# PT2399.net
KiCad netlist of a schematic drawn in Altium Designer
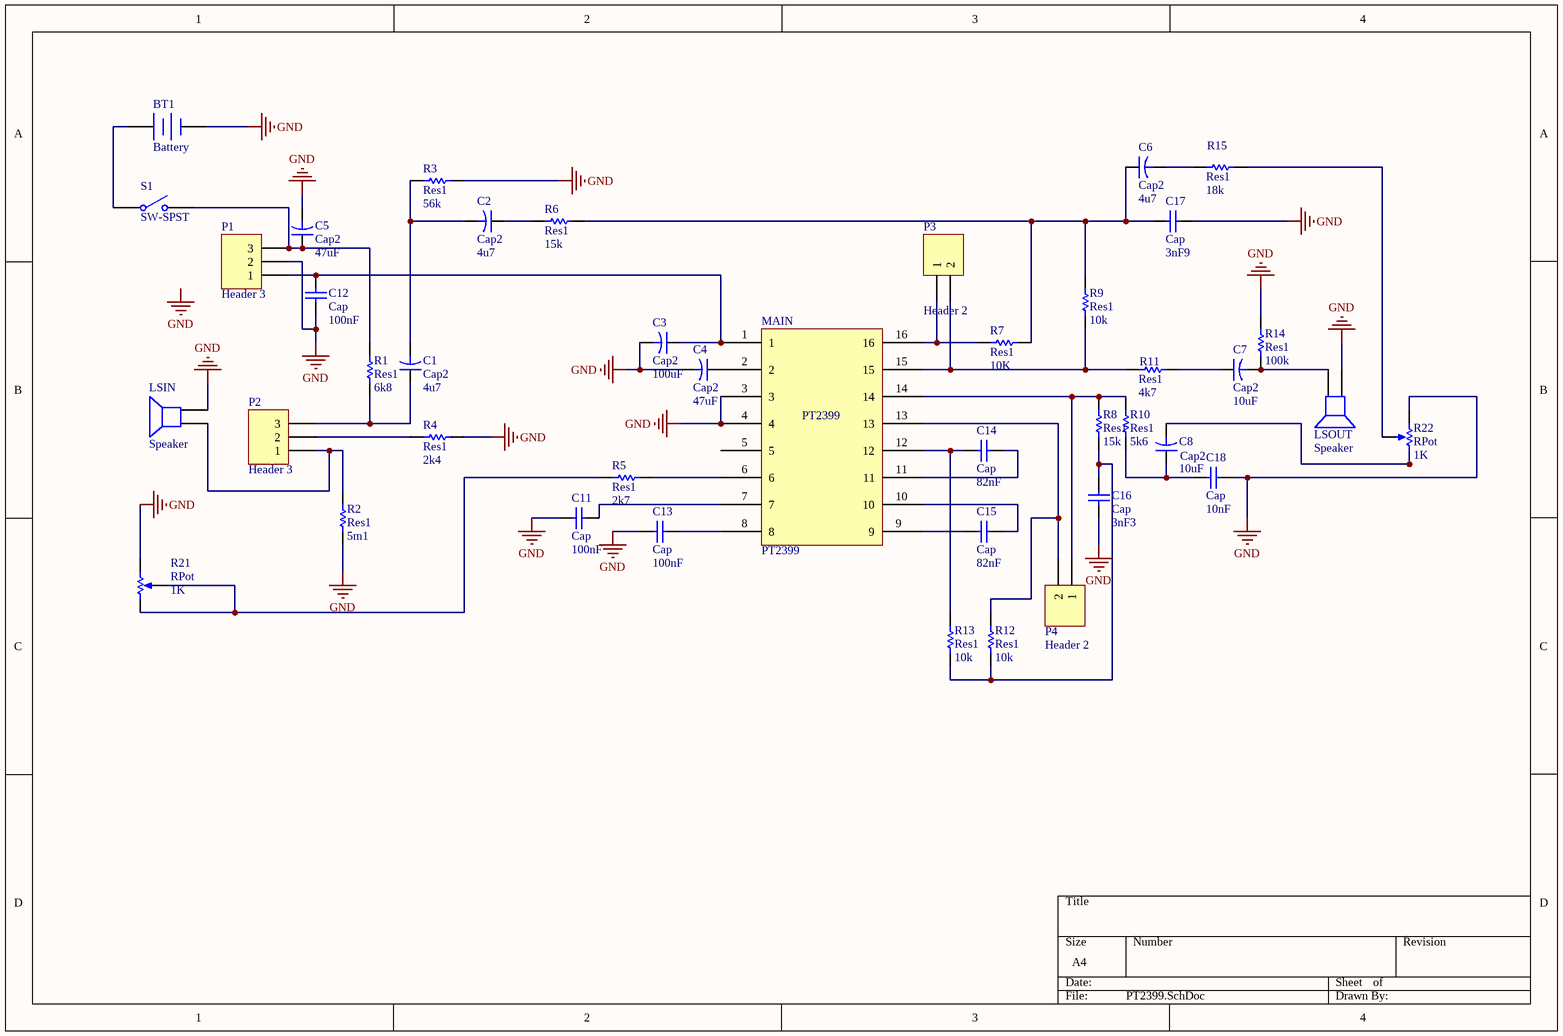
[diagram p0: PT2399.SchDoc]

(export (version "E")
  (design (tool "Eeschema 10.0.6"))
  (components
    (comp (ref "BT1")
      (value "Battery")
      (footprint "BAT-2")
      (description "Multicell Battery")
      (fields (field (name "PUBLISHER") "Altium Limited"))
      (libsource (lib "Miscellaneous Devices") (part "Battery"))
    )
    (comp (ref "C1")
      (value "Cap2")
      (footprint "CAPR5-4X5")
      (description "Capacitor")
      (fields (field (name "ALTIUM_VALUE") "4u7") (field (name "PUBLISHER") "Altium Limited"))
      (libsource (lib "Miscellaneous Devices") (part "Cap2"))
    )
    (comp (ref "C2")
      (value "Cap2")
      (footprint "CAPR5-4X5")
      (description "Capacitor")
      (fields (field (name "ALTIUM_VALUE") "4u7") (field (name "PUBLISHER") "Altium Limited"))
      (libsource (lib "Miscellaneous Devices") (part "Cap2"))
    )
    (comp (ref "C3")
      (value "Cap2")
      (footprint "CAPR5-4X5")
      (description "Capacitor")
      (fields (field (name "ALTIUM_VALUE") "100uF") (field (name "PUBLISHER") "Altium Limited"))
      (libsource (lib "Miscellaneous Devices") (part "Cap2"))
    )
    (comp (ref "C4")
      (value "Cap2")
      (footprint "CAPR5-4X5")
      (description "Capacitor")
      (fields (field (name "ALTIUM_VALUE") "47uF") (field (name "PUBLISHER") "Altium Limited"))
      (libsource (lib "Miscellaneous Devices") (part "Cap2"))
    )
    (comp (ref "C5")
      (value "Cap2")
      (footprint "CAPR5-4X5")
      (description "Capacitor")
      (fields (field (name "ALTIUM_VALUE") "47uF") (field (name "PUBLISHER") "Altium Limited"))
      (libsource (lib "Miscellaneous Devices") (part "Cap2"))
    )
    (comp (ref "C6")
      (value "Cap2")
      (footprint "CAPR5-4X5")
      (description "Capacitor")
      (fields (field (name "ALTIUM_VALUE") "4u7") (field (name "PUBLISHER") "Altium Limited"))
      (libsource (lib "Miscellaneous Devices") (part "Cap2"))
    )
    (comp (ref "C7")
      (value "Cap2")
      (footprint "CAPR5-4X5")
      (description "Capacitor")
      (fields (field (name "ALTIUM_VALUE") "10uF") (field (name "PUBLISHER") "Altium Limited"))
      (libsource (lib "Miscellaneous Devices") (part "Cap2"))
    )
    (comp (ref "C8")
      (value "Cap2")
      (footprint "CAPR5-4X5")
      (description "Capacitor")
      (fields (field (name "ALTIUM_VALUE") "10uF") (field (name "PUBLISHER") "Altium Limited"))
      (libsource (lib "Miscellaneous Devices") (part "Cap2"))
    )
    (comp (ref "C11")
      (value "Cap")
      (footprint "RAD-0.3")
      (description "Capacitor")
      (fields (field (name "ALTIUM_VALUE") "100nF") (field (name "PUBLISHER") "Altium Limited"))
      (libsource (lib "Miscellaneous Devices") (part "Cap"))
    )
    (comp (ref "C12")
      (value "Cap")
      (footprint "RAD-0.3")
      (description "Capacitor")
      (fields (field (name "ALTIUM_VALUE") "100nF") (field (name "PUBLISHER") "Altium Limited"))
      (libsource (lib "Miscellaneous Devices") (part "Cap"))
    )
    (comp (ref "C13")
      (value "Cap")
      (footprint "RAD-0.3")
      (description "Capacitor")
      (fields (field (name "ALTIUM_VALUE") "100nF") (field (name "PUBLISHER") "Altium Limited"))
      (libsource (lib "Miscellaneous Devices") (part "Cap"))
    )
    (comp (ref "C14")
      (value "Cap")
      (footprint "RAD-0.3")
      (description "Capacitor")
      (fields (field (name "ALTIUM_VALUE") "82nF") (field (name "PUBLISHER") "Altium Limited"))
      (libsource (lib "Miscellaneous Devices") (part "Cap"))
    )
    (comp (ref "C15")
      (value "Cap")
      (footprint "RAD-0.3")
      (description "Capacitor")
      (fields (field (name "ALTIUM_VALUE") "82nF") (field (name "PUBLISHER") "Altium Limited"))
      (libsource (lib "Miscellaneous Devices") (part "Cap"))
    )
    (comp (ref "C16")
      (value "Cap")
      (footprint "RAD-0.3")
      (description "Capacitor")
      (fields (field (name "ALTIUM_VALUE") "3nF3") (field (name "PUBLISHER") "Altium Limited"))
      (libsource (lib "Miscellaneous Devices") (part "Cap"))
    )
    (comp (ref "C17")
      (value "Cap")
      (footprint "RAD-0.3")
      (description "Capacitor")
      (fields (field (name "ALTIUM_VALUE") "3nF9") (field (name "PUBLISHER") "Altium Limited"))
      (libsource (lib "Miscellaneous Devices") (part "Cap"))
    )
    (comp (ref "C18")
      (value "Cap")
      (footprint "RAD-0.3")
      (description "Capacitor")
      (fields (field (name "ALTIUM_VALUE") "10nF") (field (name "PUBLISHER") "Altium Limited"))
      (libsource (lib "Miscellaneous Devices") (part "Cap"))
    )
    (comp (ref "LSIN")
      (value "Speaker")
      (footprint "PIN2")
      (description "Loudspeaker")
      (fields (field (name "PUBLISHER") "Altium Limited"))
      (libsource (lib "Miscellaneous Devices") (part "Speaker"))
    )
    (comp (ref "LSOUT")
      (value "Speaker")
      (footprint "PIN2")
      (description "Loudspeaker")
      (fields (field (name "PUBLISHER") "Altium Limited"))
      (libsource (lib "Miscellaneous Devices") (part "Speaker"))
    )
    (comp (ref "MAIN") (value "PT2399") (footprint "PT2399") (libsource (lib "Schlib1") (part "PT2399")))
    (comp (ref "P1")
      (value "Header 3")
      (footprint "HDR1X3")
      (description "Header, 3-Pin")
      (fields (field (name "PUBLISHER") "Altium Limited"))
      (libsource (lib "Miscellaneous Connectors") (part "Header 3"))
    )
    (comp (ref "P2")
      (value "Header 3")
      (footprint "HDR1X3")
      (description "Header, 3-Pin")
      (fields (field (name "PUBLISHER") "Altium Limited"))
      (libsource (lib "Miscellaneous Connectors") (part "Header 3"))
    )
    (comp (ref "P3")
      (value "Header 2")
      (footprint "HDR1X2")
      (description "Header, 2-Pin")
      (fields (field (name "PUBLISHER") "Altium Limited"))
      (libsource (lib "Miscellaneous Connectors") (part "Header 2"))
    )
    (comp (ref "P4")
      (value "Header 2")
      (footprint "HDR1X2")
      (description "Header, 2-Pin")
      (fields (field (name "PUBLISHER") "Altium Limited"))
      (libsource (lib "") (part "Header 2_1"))
    )
    (comp (ref "R1")
      (value "Res1")
      (footprint "AXIAL-0.3")
      (description "Resistor")
      (fields (field (name "ALTIUM_VALUE") "6k8") (field (name "PUBLISHER") "Altium Limited"))
      (libsource (lib "Miscellaneous Devices") (part "Res1"))
    )
    (comp (ref "R2")
      (value "Res1")
      (footprint "AXIAL-0.3")
      (description "Resistor")
      (fields (field (name "ALTIUM_VALUE") "5m1") (field (name "PUBLISHER") "Altium Limited"))
      (libsource (lib "Miscellaneous Devices") (part "Res1"))
    )
    (comp (ref "R3")
      (value "Res1")
      (footprint "AXIAL-0.3")
      (description "Resistor")
      (fields (field (name "ALTIUM_VALUE") "56k") (field (name "PUBLISHER") "Altium Limited"))
      (libsource (lib "Miscellaneous Devices") (part "Res1"))
    )
    (comp (ref "R4")
      (value "Res1")
      (footprint "AXIAL-0.3")
      (description "Resistor")
      (fields (field (name "ALTIUM_VALUE") "2k4") (field (name "PUBLISHER") "Altium Limited"))
      (libsource (lib "Miscellaneous Devices") (part "Res1"))
    )
    (comp (ref "R5")
      (value "Res1")
      (footprint "AXIAL-0.3")
      (description "Resistor")
      (fields (field (name "ALTIUM_VALUE") "2k7") (field (name "PUBLISHER") "Altium Limited"))
      (libsource (lib "Miscellaneous Devices") (part "Res1"))
    )
    (comp (ref "R6")
      (value "Res1")
      (footprint "AXIAL-0.3")
      (description "Resistor")
      (fields (field (name "ALTIUM_VALUE") "15k") (field (name "PUBLISHER") "Altium Limited"))
      (libsource (lib "Miscellaneous Devices") (part "Res1"))
    )
    (comp (ref "R7")
      (value "Res1")
      (footprint "AXIAL-0.3")
      (description "Resistor")
      (fields (field (name "ALTIUM_VALUE") "10K") (field (name "PUBLISHER") "Altium Limited"))
      (libsource (lib "Miscellaneous Devices") (part "Res1"))
    )
    (comp (ref "R8")
      (value "Res1")
      (footprint "AXIAL-0.3")
      (description "Resistor")
      (fields (field (name "ALTIUM_VALUE") "15k") (field (name "PUBLISHER") "Altium Limited"))
      (libsource (lib "Miscellaneous Devices") (part "Res1"))
    )
    (comp (ref "R9")
      (value "Res1")
      (footprint "AXIAL-0.3")
      (description "Resistor")
      (fields (field (name "ALTIUM_VALUE") "10k") (field (name "PUBLISHER") "Altium Limited"))
      (libsource (lib "Miscellaneous Devices") (part "Res1"))
    )
    (comp (ref "R10")
      (value "Res1")
      (footprint "AXIAL-0.3")
      (description "Resistor")
      (fields (field (name "ALTIUM_VALUE") "5k6") (field (name "PUBLISHER") "Altium Limited"))
      (libsource (lib "Miscellaneous Devices") (part "Res1"))
    )
    (comp (ref "R11")
      (value "Res1")
      (footprint "AXIAL-0.3")
      (description "Resistor")
      (fields (field (name "ALTIUM_VALUE") "4k7") (field (name "PUBLISHER") "Altium Limited"))
      (libsource (lib "Miscellaneous Devices") (part "Res1"))
    )
    (comp (ref "R12")
      (value "Res1")
      (footprint "AXIAL-0.3")
      (description "Resistor")
      (fields (field (name "ALTIUM_VALUE") "10k") (field (name "PUBLISHER") "Altium Limited"))
      (libsource (lib "Miscellaneous Devices") (part "Res1"))
    )
    (comp (ref "R13")
      (value "Res1")
      (footprint "AXIAL-0.3")
      (description "Resistor")
      (fields (field (name "ALTIUM_VALUE") "10k") (field (name "PUBLISHER") "Altium Limited"))
      (libsource (lib "Miscellaneous Devices") (part "Res1"))
    )
    (comp (ref "R14")
      (value "Res1")
      (footprint "AXIAL-0.3")
      (description "Resistor")
      (fields (field (name "ALTIUM_VALUE") "100k") (field (name "PUBLISHER") "Altium Limited"))
      (libsource (lib "Miscellaneous Devices") (part "Res1"))
    )
    (comp (ref "R15")
      (value "Res1")
      (footprint "AXIAL-0.3")
      (description "Resistor")
      (fields (field (name "ALTIUM_VALUE") "18k") (field (name "PUBLISHER") "Altium Limited"))
      (libsource (lib "Miscellaneous Devices") (part "Res1"))
    )
    (comp (ref "R21")
      (value "RPot")
      (footprint "7805")
      (description "Potentiometer")
      (fields (field (name "ALTIUM_VALUE") "1K") (field (name "PUBLISHER") "Altium Limited"))
      (libsource (lib "Miscellaneous Devices") (part "RPot"))
    )
    (comp (ref "R22")
      (value "RPot")
      (footprint "7805")
      (description "Potentiometer")
      (fields (field (name "ALTIUM_VALUE") "1K") (field (name "PUBLISHER") "Altium Limited"))
      (libsource (lib "Miscellaneous Devices") (part "RPot"))
    )
    (comp (ref "S1")
      (value "SW-SPST")
      (footprint "SPST-2")
      (description "Single-Pole, Single-Throw Switch")
      (fields (field (name "PUBLISHER") "Altium Limited"))
      (libsource (lib "Miscellaneous Devices") (part "SW-SPST"))
    )
  )
  (nets
    (net (code "1") (name "GND") (class "Default")
      (node (ref "BT1") (pin "2") (pinfunction "-_2") (pintype "passive"))
      (node (ref "C11") (pin "1") (pinfunction "1_1") (pintype "passive"))
      (node (ref "C12") (pin "1") (pinfunction "1_1") (pintype "passive"))
      (node (ref "C13") (pin "1") (pinfunction "1_1") (pintype "passive"))
      (node (ref "C16") (pin "1") (pinfunction "1_1") (pintype "passive"))
      (node (ref "C17") (pin "1") (pinfunction "1_1") (pintype "passive"))
      (node (ref "C18") (pin "2") (pinfunction "2_2") (pintype "passive"))
      (node (ref "C3") (pin "2") (pinfunction "2_2") (pintype "passive"))
      (node (ref "C4") (pin "2") (pinfunction "2_2") (pintype "passive"))
      (node (ref "C5") (pin "2") (pinfunction "2_2") (pintype "passive"))
      (node (ref "LSIN") (pin "2") (pinfunction "2_2") (pintype "passive"))
      (node (ref "LSOUT") (pin "1") (pinfunction "1_1") (pintype "passive"))
      (node (ref "MAIN") (pin "3") (pinfunction "3_3") (pintype "passive"))
      (node (ref "MAIN") (pin "4") (pinfunction "4_4") (pintype "passive"))
      (node (ref "P1") (pin "2") (pinfunction "2_2") (pintype "passive"))
      (node (ref "R14") (pin "2") (pinfunction "2_2") (pintype "passive"))
      (node (ref "R2") (pin "1") (pinfunction "1_1") (pintype "passive"))
      (node (ref "R21") (pin "2") (pinfunction "BOT_2") (pintype "passive"))
      (node (ref "R22") (pin "1") (pinfunction "TOP_1") (pintype "passive"))
      (node (ref "R3") (pin "1") (pinfunction "1_1") (pintype "passive"))
      (node (ref "R4") (pin "2") (pinfunction "2_2") (pintype "passive"))
    )
    (net (code "2") (name "Net-(BT1-+)") (class "Default")
      (node (ref "BT1") (pin "1") (pinfunction "+_1") (pintype "passive"))
      (node (ref "S1") (pin "1") (pinfunction "COMMON_1") (pintype "passive"))
    )
    (net (code "3") (name "Net-(C1-Pad1)") (class "Default")
      (node (ref "C1") (pin "1") (pinfunction "1_1") (pintype "passive"))
      (node (ref "P2") (pin "3") (pinfunction "3_3") (pintype "passive"))
      (node (ref "R1") (pin "1") (pinfunction "1_1") (pintype "passive"))
    )
    (net (code "4") (name "Net-(C1-Pad2)") (class "Default")
      (node (ref "C1") (pin "2") (pinfunction "2_2") (pintype "passive"))
      (node (ref "C2") (pin "2") (pinfunction "2_2") (pintype "passive"))
      (node (ref "R3") (pin "2") (pinfunction "2_2") (pintype "passive"))
    )
    (net (code "5") (name "Net-(C2-Pad1)") (class "Default")
      (node (ref "C2") (pin "1") (pinfunction "1_1") (pintype "passive"))
      (node (ref "R6") (pin "1") (pinfunction "1_1") (pintype "passive"))
    )
    (net (code "6") (name "Net-(C4-Pad1)") (class "Default")
      (node (ref "C4") (pin "1") (pinfunction "1_1") (pintype "passive"))
      (node (ref "MAIN") (pin "2") (pinfunction "2_2") (pintype "passive"))
    )
    (net (code "7") (name "Net-(C6-Pad2)") (class "Default")
      (node (ref "C6") (pin "2") (pinfunction "2_2") (pintype "passive"))
      (node (ref "R15") (pin "1") (pinfunction "1_1") (pintype "passive"))
    )
    (net (code "8") (name "Net-(C7-Pad1)") (class "Default")
      (node (ref "C7") (pin "1") (pinfunction "1_1") (pintype "passive"))
      (node (ref "R11") (pin "2") (pinfunction "2_2") (pintype "passive"))
    )
    (net (code "9") (name "Net-(C7-Pad2)") (class "Default")
      (node (ref "C7") (pin "2") (pinfunction "2_2") (pintype "passive"))
      (node (ref "LSOUT") (pin "2") (pinfunction "2_2") (pintype "passive"))
      (node (ref "R14") (pin "1") (pinfunction "1_1") (pintype "passive"))
    )
    (net (code "10") (name "Net-(C11-Pad2)") (class "Default")
      (node (ref "C11") (pin "2") (pinfunction "2_2") (pintype "passive"))
      (node (ref "MAIN") (pin "7") (pinfunction "7_7") (pintype "passive"))
    )
    (net (code "11") (name "Net-(C12-Pad2)") (class "Default")
      (node (ref "C12") (pin "2") (pinfunction "2_2") (pintype "passive"))
      (node (ref "C3") (pin "1") (pinfunction "1_1") (pintype "passive"))
      (node (ref "MAIN") (pin "1") (pinfunction "1_1") (pintype "passive"))
      (node (ref "P1") (pin "1") (pinfunction "1_1") (pintype "passive"))
    )
    (net (code "12") (name "Net-(C13-Pad2)") (class "Default")
      (node (ref "C13") (pin "2") (pinfunction "2_2") (pintype "passive"))
      (node (ref "MAIN") (pin "8") (pinfunction "8_8") (pintype "passive"))
    )
    (net (code "13") (name "Net-(C14-Pad1)") (class "Default")
      (node (ref "C14") (pin "1") (pinfunction "1_1") (pintype "passive"))
      (node (ref "MAIN") (pin "12") (pinfunction "12_12") (pintype "passive"))
      (node (ref "R13") (pin "2") (pinfunction "2_2") (pintype "passive"))
    )
    (net (code "14") (name "Net-(C14-Pad2)") (class "Default")
      (node (ref "C14") (pin "2") (pinfunction "2_2") (pintype "passive"))
      (node (ref "MAIN") (pin "11") (pinfunction "11_11") (pintype "passive"))
    )
    (net (code "15") (name "Net-(C15-Pad1)") (class "Default")
      (node (ref "C15") (pin "1") (pinfunction "1_1") (pintype "passive"))
      (node (ref "MAIN") (pin "9") (pinfunction "9_9") (pintype "passive"))
    )
    (net (code "16") (name "Net-(C15-Pad2)") (class "Default")
      (node (ref "C15") (pin "2") (pinfunction "2_2") (pintype "passive"))
      (node (ref "MAIN") (pin "10") (pinfunction "10_10") (pintype "passive"))
    )
    (net (code "17") (name "Net-(C16-Pad2)") (class "Default")
      (node (ref "C16") (pin "2") (pinfunction "2_2") (pintype "passive"))
      (node (ref "R12") (pin "2") (pinfunction "2_2") (pintype "passive"))
      (node (ref "R13") (pin "1") (pinfunction "1_1") (pintype "passive"))
      (node (ref "R8") (pin "1") (pinfunction "1_1") (pintype "passive"))
    )
    (net (code "18") (name "Net-(C17-Pad2)") (class "Default")
      (node (ref "C17") (pin "2") (pinfunction "2_2") (pintype "passive"))
      (node (ref "C6") (pin "1") (pinfunction "1_1") (pintype "passive"))
      (node (ref "R6") (pin "2") (pinfunction "2_2") (pintype "passive"))
      (node (ref "R7") (pin "2") (pinfunction "2_2") (pintype "passive"))
      (node (ref "R9") (pin "2") (pinfunction "2_2") (pintype "passive"))
    )
    (net (code "19") (name "Net-(C18-Pad1)") (class "Default")
      (node (ref "C18") (pin "1") (pinfunction "1_1") (pintype "passive"))
      (node (ref "C8") (pin "1") (pinfunction "1_1") (pintype "passive"))
      (node (ref "R10") (pin "1") (pinfunction "1_1") (pintype "passive"))
    )
    (net (code "20") (name "Net-(LSIN-Pad1)") (class "Default")
      (node (ref "LSIN") (pin "1") (pinfunction "1_1") (pintype "passive"))
      (node (ref "P2") (pin "1") (pinfunction "1_1") (pintype "passive"))
      (node (ref "R2") (pin "2") (pinfunction "2_2") (pintype "passive"))
    )
    (net (code "21") (name "Net-(MAIN-Pad6)") (class "Default")
      (node (ref "MAIN") (pin "6") (pinfunction "6_6") (pintype "passive"))
      (node (ref "R5") (pin "1") (pinfunction "1_1") (pintype "passive"))
    )
    (net (code "22") (name "Net-(MAIN-Pad13)") (class "Default")
      (node (ref "MAIN") (pin "13") (pinfunction "13_13") (pintype "passive"))
      (node (ref "P4") (pin "2") (pinfunction "2_2") (pintype "passive"))
      (node (ref "R12") (pin "1") (pinfunction "1_1") (pintype "passive"))
    )
    (net (code "23") (name "Net-(MAIN-Pad14)") (class "Default")
      (node (ref "MAIN") (pin "14") (pinfunction "14_14") (pintype "passive"))
      (node (ref "P4") (pin "1") (pinfunction "1_1") (pintype "passive"))
      (node (ref "R10") (pin "2") (pinfunction "2_2") (pintype "passive"))
      (node (ref "R8") (pin "2") (pinfunction "2_2") (pintype "passive"))
    )
    (net (code "24") (name "Net-(MAIN-Pad15)") (class "Default")
      (node (ref "MAIN") (pin "15") (pinfunction "15_15") (pintype "passive"))
      (node (ref "P3") (pin "2") (pinfunction "2_2") (pintype "passive"))
      (node (ref "R11") (pin "1") (pinfunction "1_1") (pintype "passive"))
      (node (ref "R9") (pin "1") (pinfunction "1_1") (pintype "passive"))
    )
    (net (code "25") (name "Net-(MAIN-Pad16)") (class "Default")
      (node (ref "MAIN") (pin "16") (pinfunction "16_16") (pintype "passive"))
      (node (ref "P3") (pin "1") (pinfunction "1_1") (pintype "passive"))
      (node (ref "R7") (pin "1") (pinfunction "1_1") (pintype "passive"))
    )
    (net (code "26") (name "Net-(P2-Pad2)") (class "Default")
      (node (ref "P2") (pin "2") (pinfunction "2_2") (pintype "passive"))
      (node (ref "R4") (pin "1") (pinfunction "1_1") (pintype "passive"))
    )
    (net (code "27") (name "Net-(R21-TAP)") (class "Default")
      (node (ref "R21") (pin "1") (pinfunction "TOP_1") (pintype "passive"))
      (node (ref "R21") (pin "3") (pinfunction "TAP_3") (pintype "passive"))
      (node (ref "R5") (pin "2") (pinfunction "2_2") (pintype "passive"))
    )
    (net (code "28") (name "Net-(R22-BOT)") (class "Default")
      (node (ref "C8") (pin "2") (pinfunction "2_2") (pintype "passive"))
      (node (ref "R22") (pin "2") (pinfunction "BOT_2") (pintype "passive"))
    )
    (net (code "29") (name "Net-(R22-TAP)") (class "Default")
      (node (ref "R15") (pin "2") (pinfunction "2_2") (pintype "passive"))
      (node (ref "R22") (pin "3") (pinfunction "TAP_3") (pintype "passive"))
    )
    (net (code "30") (name "Net-(S1-NO)") (class "Default")
      (node (ref "C5") (pin "1") (pinfunction "1_1") (pintype "passive"))
      (node (ref "P1") (pin "3") (pinfunction "3_3") (pintype "passive"))
      (node (ref "R1") (pin "2") (pinfunction "2_2") (pintype "passive"))
      (node (ref "S1") (pin "2") (pinfunction "NO_2") (pintype "passive"))
    )
    (net (code "31") (name "unconnected-(MAIN-Pad5)") (class "Default")
      (node (ref "MAIN") (pin "5") (pinfunction "5_5") (pintype "passive"))
    )
  )
)
